# 10X_SD_CARD_READER_SCH_SHEET_4.net
KiCad netlist of a schematic drawn in Altium Designer
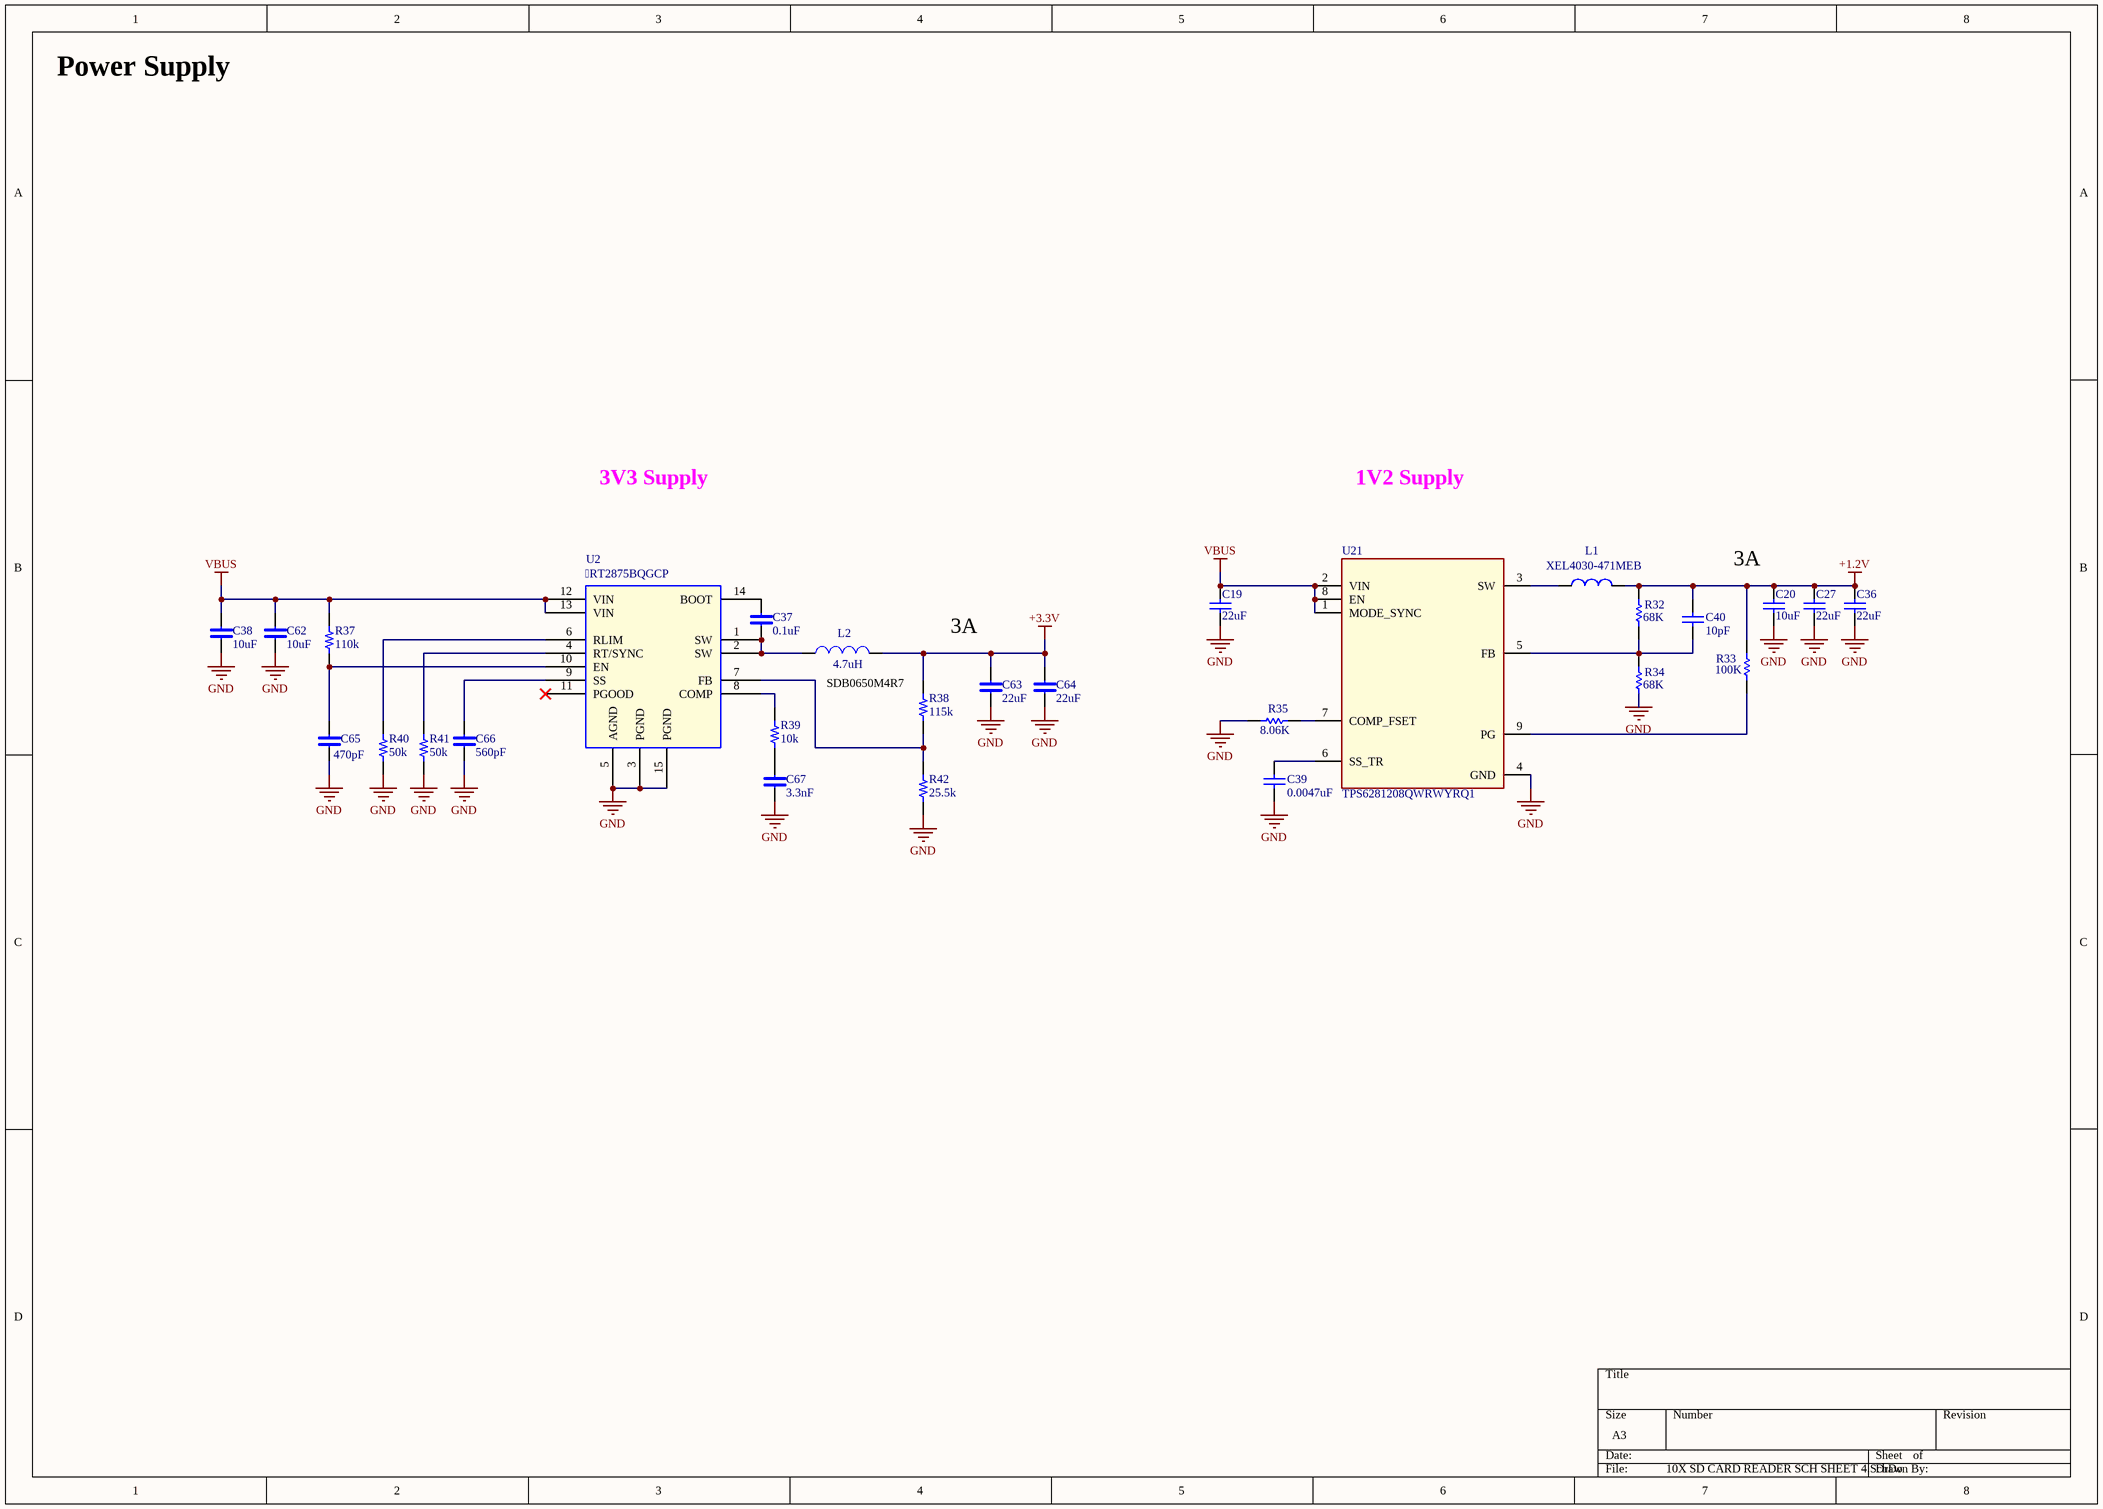
[diagram p0: 10X SD CARD READER SCH SHEET 4.SchDoc]

(export (version "E")
  (design (tool "Eeschema 10.0.6"))
  (components
    (comp (ref "C19")
      (value "22uF")
      (footprint "CAPC3216X180N")
      (description "Capacitor")
      (fields (field (name "PUBLISHER") "Altium Limited"))
      (libsource (lib "Miscellaneous Devices") (part "Cap"))
    )
    (comp (ref "C20")
      (value "10uF")
      (footprint "CAPC1608X100N")
      (description "Capacitor")
      (fields (field (name "PUBLISHER") "Altium Limited"))
      (libsource (lib "Miscellaneous Devices") (part "Cap"))
    )
    (comp (ref "C27")
      (value "22uF")
      (footprint "CAPC3216X180N")
      (description "Capacitor")
      (fields (field (name "PUBLISHER") "Altium Limited"))
      (libsource (lib "Miscellaneous Devices") (part "Cap"))
    )
    (comp (ref "C36")
      (value "22uF")
      (footprint "CAPC3216X180N")
      (description "Capacitor")
      (fields (field (name "PUBLISHER") "Altium Limited"))
      (libsource (lib "Miscellaneous Devices") (part "Cap"))
    )
    (comp (ref "C37")
      (value "0.1uF")
      (footprint "C-0402/1005")
      (description "CAP CER 10UF 25V X5R 1206")
      (fields (field (name "MFR. PART NO.") "C1206C106M3PACTU"))
      (libsource (lib "Custom_Library") (part "CAP 1206/3216"))
    )
    (comp (ref "C38")
      (value "10uF")
      (footprint "C-1206/3216")
      (description "CAP CER 10UF 25V X5R 1206")
      (fields (field (name "MFR. PART NO.") "C1206C106M3PACTU"))
      (libsource (lib "Custom_Library") (part "CAP 1206/3216"))
    )
    (comp (ref "C39")
      (value "0.0047uF")
      (footprint "C-0402/1005")
      (description "Capacitor")
      (fields (field (name "Comment") "0.1uF") (field (name "PUBLISHER") "Altium Limited"))
      (libsource (lib "Miscellaneous Devices") (part "Cap"))
    )
    (comp (ref "C40")
      (value "10pF")
      (footprint "C-0402/1005")
      (description "Capacitor")
      (fields (field (name "Comment") "0.1uF") (field (name "PUBLISHER") "Altium Limited"))
      (libsource (lib "Miscellaneous Devices") (part "Cap"))
    )
    (comp (ref "C62")
      (value "10uF")
      (footprint "C-1206/3216")
      (description "CAP CER 10UF 25V X5R 1206")
      (fields (field (name "MFR. PART NO.") "C1206C106M3PACTU"))
      (libsource (lib "Custom_Library") (part "CAP 1206/3216"))
    )
    (comp (ref "C63")
      (value "22uF")
      (footprint "C-1206/3216")
      (description "CAP CER 0.1UF 50V X7R 0402")
      (fields (field (name "MFR. PART NO.") "UMK105B7104KV-FR"))
      (libsource (lib "Custom_Library") (part "Capacitor-NonPolar"))
    )
    (comp (ref "C64")
      (value "22uF")
      (footprint "C-1206/3216")
      (description "CAP CER 0.1UF 50V X7R 0402")
      (fields (field (name "MFR. PART NO.") "UMK105B7104KV-FR"))
      (libsource (lib "Custom_Library") (part "Capacitor-NonPolar"))
    )
    (comp (ref "C65")
      (value "470pF")
      (footprint "C-0402/1005")
      (description "CAP CER 10UF 25V X5R 1206")
      (fields (field (name "MFR. PART NO.") "C1206C106M3PACTU"))
      (libsource (lib "Custom_Library") (part "CAP 1206/3216"))
    )
    (comp (ref "C66")
      (value "560pF")
      (footprint "C-0402/1005")
      (description "CAP CER 10UF 25V X5R 1206")
      (fields (field (name "MFR. PART NO.") "C1206C106M3PACTU"))
      (libsource (lib "Custom_Library") (part "CAP 1206/3216"))
    )
    (comp (ref "C67")
      (value "3.3nF")
      (footprint "C-0402/1005")
      (description "CAP CER 10UF 25V X5R 1206")
      (fields (field (name "MFR. PART NO.") "C1206C106M3PACTU"))
      (libsource (lib "Custom_Library") (part "CAP 1206/3216"))
    )
    (comp (ref "L1")
      (value "XEL4030-471MEB")
      (footprint "IND_XEL4030_3.1_COC")
      (description "Inductor with Inductance: 1uH Tol. +/-20%, Package: 0805 _2012_")
      (fields (field (name "MP") "LQM21PN1R0MC0D") (field (name "MF") "Murata"))
      (libsource (lib "LQM21PN1R0MC0D") (part "LQM21PN1R0MC0D"))
    )
    (comp (ref "L2")
      (value "4.7uH")
      (footprint "IND_SPM6550T-4R7M")
      (description "Power inductor 4.7uH Isat=7A")
      (fields (field (name "MANUFACTURER") "VIKING"))
      (libsource (lib "*") (part "INDUCTOR_2"))
    )
    (comp (ref "R32")
      (value "68K")
      (footprint "R-0402/1005")
      (description "Resistor")
      (fields (field (name "PUBLISHER") "Altium Limited"))
      (libsource (lib "Miscellaneous Devices") (part "Res1"))
    )
    (comp (ref "R33")
      (value "100K")
      (footprint "R-0402/1005")
      (description "Resistor")
      (fields (field (name "PUBLISHER") "Altium Limited"))
      (libsource (lib "Miscellaneous Devices") (part "Res1"))
    )
    (comp (ref "R34")
      (value "68K")
      (footprint "R-0402/1005")
      (description "Resistor")
      (fields (field (name "PUBLISHER") "Altium Limited"))
      (libsource (lib "Miscellaneous Devices") (part "Res1"))
    )
    (comp (ref "R35")
      (value "8.06K")
      (footprint "R-0402/1005")
      (description "Resistor")
      (fields (field (name "PUBLISHER") "Altium Limited"))
      (libsource (lib "Miscellaneous Devices") (part "Res1"))
    )
    (comp (ref "R37")
      (value "110k")
      (footprint "R-0402/1005")
      (description "RES SMD 51 OHM 0.5% 1/16W 0402")
      (fields (field (name "MFR. PART NO.") "ERA-2AED510X"))
      (libsource (lib "Custom_Library") (part "Resistor"))
    )
    (comp (ref "R38")
      (value "115k")
      (footprint "R-0402/1005")
      (description "RES SMD 51 OHM 0.5% 1/16W 0402")
      (fields (field (name "MFR. PART NO.") "ERA-2AED510X"))
      (libsource (lib "Custom_Library") (part "Resistor"))
    )
    (comp (ref "R39")
      (value "10k")
      (footprint "R-0402/1005")
      (description "RES SMD 51 OHM 0.5% 1/16W 0402")
      (fields (field (name "MFR. PART NO.") "ERA-2AED510X"))
      (libsource (lib "Custom_Library") (part "Resistor"))
    )
    (comp (ref "R40")
      (value "50k")
      (footprint "R-0402/1005")
      (description "RES SMD 51 OHM 0.5% 1/16W 0402")
      (fields (field (name "MFR. PART NO.") "ERA-2AED510X"))
      (libsource (lib "Custom_Library") (part "Resistor"))
    )
    (comp (ref "R41")
      (value "50k")
      (footprint "R-0402/1005")
      (description "RES SMD 51 OHM 0.5% 1/16W 0402")
      (fields (field (name "MFR. PART NO.") "ERA-2AED510X"))
      (libsource (lib "Custom_Library") (part "Resistor"))
    )
    (comp (ref "R42")
      (value "25.5k")
      (footprint "R-0402/1005")
      (description "RES SMD 51 OHM 0.5% 1/16W 0402")
      (fields (field (name "MFR. PART NO.") "ERA-2AED510X"))
      (libsource (lib "Custom_Library") (part "Resistor"))
    )
    (comp (ref "U2")
      (value "RT2875BQGCP")
      (footprint "TSSOP-14")
      (description "DC2DC chip")
      (fields (field (name "MANUFACTURER") "RICHTECK"))
      (libsource (lib "*") (part "RT2875A/B"))
    )
    (comp (ref "U21")
      (value "TPS6281208QWRWYRQ1")
      (footprint "RWY0009A")
      (description "No Description Available")
      (fields (field (name "COPYRIGHT") "Copyright (C) 2023 Ultra Librarian. All rights reserved."))
      (libsource (lib "TPS6281208QWRWYRQ1") (part "TPS6281208QWRWYRQ1"))
    )
  )
  (nets
    (net (code "1") (name "+1.2V") (class "Default")
      (node (ref "C20") (pin "2") (pinfunction "2_2") (pintype "passive"))
      (node (ref "C27") (pin "2") (pinfunction "2_2") (pintype "passive"))
      (node (ref "C36") (pin "2") (pinfunction "2_2") (pintype "passive"))
      (node (ref "C40") (pin "1") (pinfunction "1_1") (pintype "passive"))
      (node (ref "L1") (pin "2") (pinfunction "2_2") (pintype "passive"))
      (node (ref "R32") (pin "2") (pinfunction "2_2") (pintype "passive"))
      (node (ref "R33") (pin "2") (pinfunction "2_2") (pintype "passive"))
    )
    (net (code "2") (name "+3.3V") (class "Default")
      (node (ref "C63") (pin "1") (pinfunction "1_1") (pintype "passive"))
      (node (ref "C64") (pin "1") (pinfunction "1_1") (pintype "passive"))
      (node (ref "L2") (pin "2") (pinfunction "2_2") (pintype "passive"))
      (node (ref "R38") (pin "2") (pinfunction "2_2") (pintype "passive"))
    )
    (net (code "3") (name "GND") (class "Default")
      (node (ref "C19") (pin "1") (pinfunction "1_1") (pintype "passive"))
      (node (ref "C20") (pin "1") (pinfunction "1_1") (pintype "passive"))
      (node (ref "C27") (pin "1") (pinfunction "1_1") (pintype "passive"))
      (node (ref "C36") (pin "1") (pinfunction "1_1") (pintype "passive"))
      (node (ref "C38") (pin "1") (pinfunction "1_1") (pintype "passive"))
      (node (ref "C39") (pin "2") (pinfunction "2_2") (pintype "passive"))
      (node (ref "C62") (pin "1") (pinfunction "1_1") (pintype "passive"))
      (node (ref "C63") (pin "2") (pinfunction "2_2") (pintype "passive"))
      (node (ref "C64") (pin "2") (pinfunction "2_2") (pintype "passive"))
      (node (ref "C65") (pin "1") (pinfunction "1_1") (pintype "passive"))
      (node (ref "C66") (pin "1") (pinfunction "1_1") (pintype "passive"))
      (node (ref "C67") (pin "1") (pinfunction "1_1") (pintype "passive"))
      (node (ref "R34") (pin "1") (pinfunction "1_1") (pintype "passive"))
      (node (ref "R35") (pin "2") (pinfunction "2_2") (pintype "passive"))
      (node (ref "R40") (pin "1") (pinfunction "1_1") (pintype "passive"))
      (node (ref "R41") (pin "1") (pinfunction "1_1") (pintype "passive"))
      (node (ref "R42") (pin "1") (pinfunction "1_1") (pintype "passive"))
      (node (ref "U2") (pin "15") (pinfunction "PGND_15") (pintype "passive"))
      (node (ref "U2") (pin "3") (pinfunction "PGND_3") (pintype "passive"))
      (node (ref "U2") (pin "5") (pinfunction "AGND_5") (pintype "passive"))
      (node (ref "U21") (pin "4") (pinfunction "GND_4") (pintype "passive"))
    )
    (net (code "4") (name "Net-(C37-Pad1)") (class "Default")
      (node (ref "C37") (pin "1") (pinfunction "1_1") (pintype "passive"))
      (node (ref "L2") (pin "1") (pinfunction "1_1") (pintype "passive"))
      (node (ref "U2") (pin "1") (pinfunction "SW_1") (pintype "passive"))
      (node (ref "U2") (pin "2") (pinfunction "SW_2") (pintype "passive"))
    )
    (net (code "5") (name "Net-(C67-Pad2)") (class "Default")
      (node (ref "C67") (pin "2") (pinfunction "2_2") (pintype "passive"))
      (node (ref "R39") (pin "1") (pinfunction "1_1") (pintype "passive"))
    )
    (net (code "6") (name "Net-(U2-BOOT)") (class "Default")
      (node (ref "C37") (pin "2") (pinfunction "2_2") (pintype "passive"))
      (node (ref "U2") (pin "14") (pinfunction "BOOT_14") (pintype "passive"))
    )
    (net (code "7") (name "Net-(U2-COMP)") (class "Default")
      (node (ref "R39") (pin "2") (pinfunction "2_2") (pintype "passive"))
      (node (ref "U2") (pin "8") (pinfunction "COMP_8") (pintype "passive"))
    )
    (net (code "8") (name "Net-(U2-EN)") (class "Default")
      (node (ref "C65") (pin "2") (pinfunction "2_2") (pintype "passive"))
      (node (ref "R37") (pin "1") (pinfunction "1_1") (pintype "passive"))
      (node (ref "U2") (pin "10") (pinfunction "EN_10") (pintype "passive"))
    )
    (net (code "9") (name "Net-(U2-FB)") (class "Default")
      (node (ref "R38") (pin "1") (pinfunction "1_1") (pintype "passive"))
      (node (ref "R42") (pin "2") (pinfunction "2_2") (pintype "passive"))
      (node (ref "U2") (pin "7") (pinfunction "FB_7") (pintype "passive"))
    )
    (net (code "10") (name "Net-(U2-RLIM)") (class "Default")
      (node (ref "R40") (pin "2") (pinfunction "2_2") (pintype "passive"))
      (node (ref "U2") (pin "6") (pinfunction "RLIM_6") (pintype "passive"))
    )
    (net (code "11") (name "Net-(U2-RT{slash}SYNC)") (class "Default")
      (node (ref "R41") (pin "2") (pinfunction "2_2") (pintype "passive"))
      (node (ref "U2") (pin "4") (pinfunction "RT/SYNC_4") (pintype "passive"))
    )
    (net (code "12") (name "Net-(U2-SS)") (class "Default")
      (node (ref "C66") (pin "2") (pinfunction "2_2") (pintype "passive"))
      (node (ref "U2") (pin "9") (pinfunction "SS_9") (pintype "passive"))
    )
    (net (code "13") (name "Net-(U21-COMP_FSET)") (class "Default")
      (node (ref "R35") (pin "1") (pinfunction "1_1") (pintype "passive"))
      (node (ref "U21") (pin "7") (pinfunction "COMP_FSET_7") (pintype "passive"))
    )
    (net (code "14") (name "Net-(U21-FB)") (class "Default")
      (node (ref "C40") (pin "2") (pinfunction "2_2") (pintype "passive"))
      (node (ref "R32") (pin "1") (pinfunction "1_1") (pintype "passive"))
      (node (ref "R34") (pin "2") (pinfunction "2_2") (pintype "passive"))
      (node (ref "U21") (pin "5") (pinfunction "FB_5") (pintype "passive"))
    )
    (net (code "15") (name "Net-(U21-PG)") (class "Default")
      (node (ref "R33") (pin "1") (pinfunction "1_1") (pintype "passive"))
      (node (ref "U21") (pin "9") (pinfunction "PG_9") (pintype "passive"))
    )
    (net (code "16") (name "Net-(U21-SS_TR)") (class "Default")
      (node (ref "C39") (pin "1") (pinfunction "1_1") (pintype "passive"))
      (node (ref "U21") (pin "6") (pinfunction "SS_TR_6") (pintype "passive"))
    )
    (net (code "17") (name "Net-(U21-SW)") (class "Default")
      (node (ref "L1") (pin "1") (pinfunction "1_1") (pintype "passive"))
      (node (ref "U21") (pin "3") (pinfunction "SW_3") (pintype "passive"))
    )
    (net (code "18") (name "VBUS") (class "Default")
      (node (ref "C19") (pin "2") (pinfunction "2_2") (pintype "passive"))
      (node (ref "C38") (pin "2") (pinfunction "2_2") (pintype "passive"))
      (node (ref "C62") (pin "2") (pinfunction "2_2") (pintype "passive"))
      (node (ref "R37") (pin "2") (pinfunction "2_2") (pintype "passive"))
      (node (ref "U2") (pin "12") (pinfunction "VIN_12") (pintype "passive"))
      (node (ref "U2") (pin "13") (pinfunction "VIN_13") (pintype "passive"))
      (node (ref "U21") (pin "1") (pinfunction "MODE_SYNC_1") (pintype "passive"))
      (node (ref "U21") (pin "2") (pinfunction "VIN_2") (pintype "passive"))
      (node (ref "U21") (pin "8") (pinfunction "EN_8") (pintype "passive"))
    )
    (net (code "19") (name "unconnected-(U2-PGOOD-Pad11)") (class "Default")
      (node (ref "U2") (pin "11") (pinfunction "PGOOD_11") (pintype "passive+no_connect"))
    )
  )
)
